# 00_BoardDiagramEntryConn.net
KiCad netlist of a schematic drawn in Altium Designer
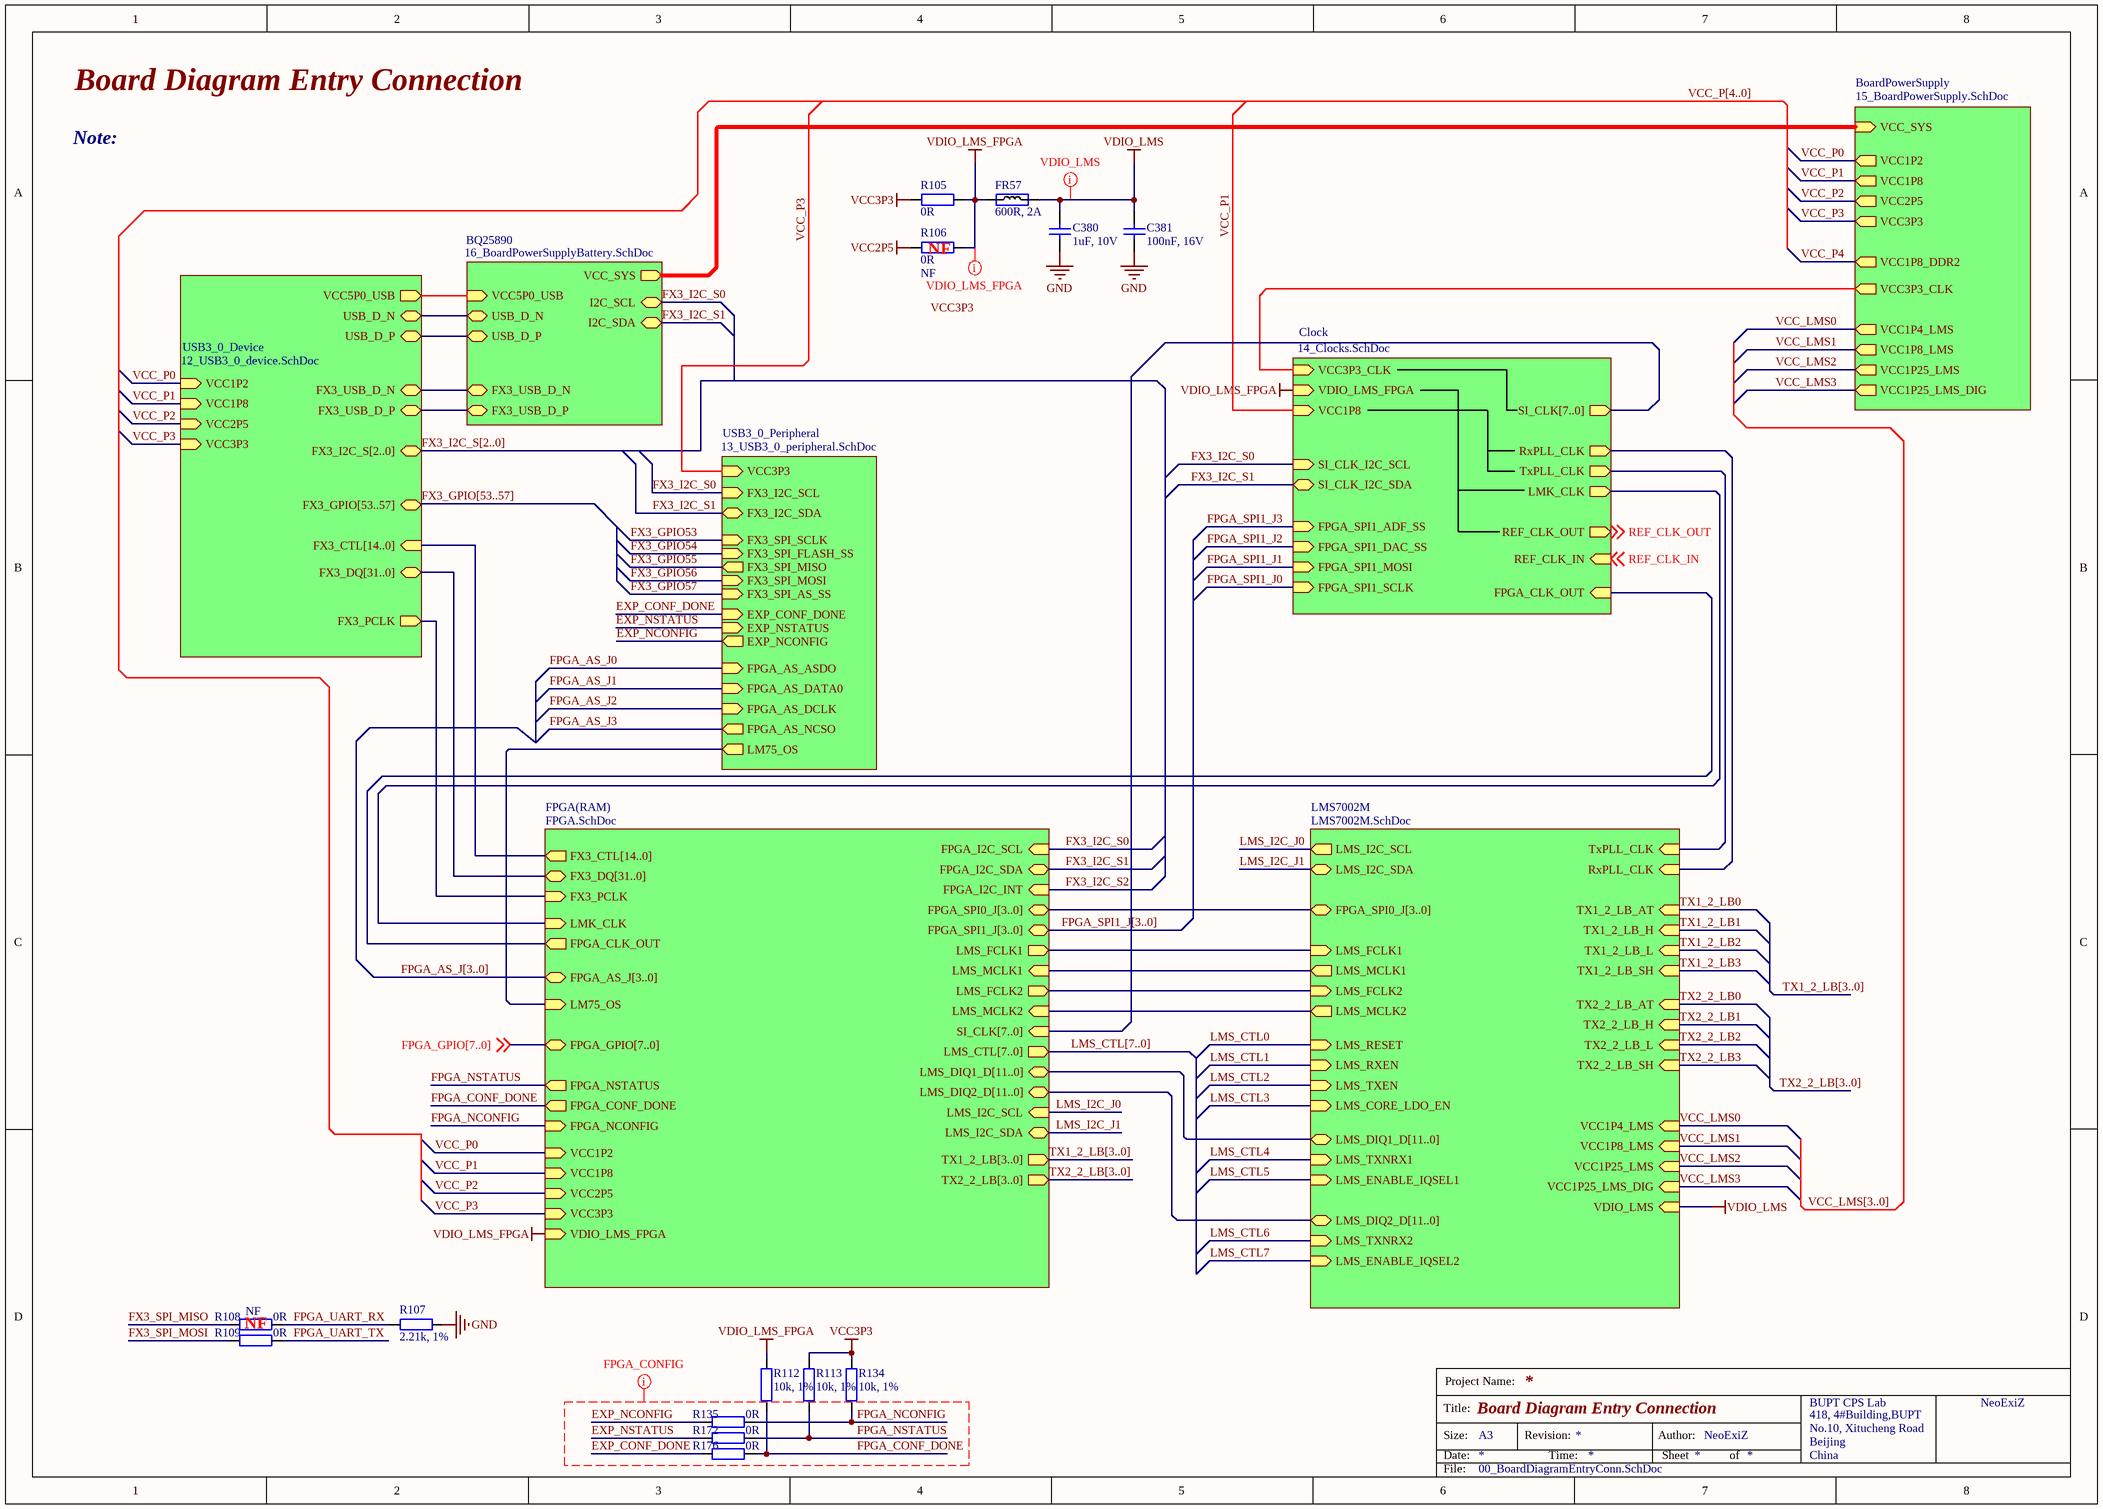
[diagram p0: 00_BoardDiagramEntryConn.SchDoc]

(export (version "E")
  (design (tool "Eeschema 10.0.6"))
  (components
    (comp (ref "C380")
      (value "1uF, 10V")
      (footprint "CAP0402")
      (fields (field (name "MANUFACTURER") "TDK"))
      (libsource (lib "LimeMicroAltiumLib_schLib") (part "Cap_0402"))
    )
    (comp (ref "C381")
      (value "100nF, 16V")
      (footprint "CAP0402")
      (fields
        (field (name "MANUFACTURER") "Murata Electronics")
        (field (name "TOLERANCE") "10 %")
        (field (name "MANUFACTURER PART NUMBER") "GRM155R71C104KA88D")
      )
      (libsource (lib "LimeMicroAltiumLib_schLib") (part "Cap_0402"))
    )
    (comp (ref "FR57")
      (value "600R, 2A")
      (footprint "RES0805")
      (fields (field (name "MANUFACTURER") "TDK Corporation"))
      (libsource (lib "LimeMicroAltiumLib_schLib") (part "Ferrite"))
    )
    (comp (ref "R105")
      (value "0R")
      (footprint "RES0402")
      (fields (field (name "MANUFACTURER") "Yageo") (field (name "TOLERANCE") "Jumper"))
      (libsource (lib "LimeMicroAltiumLib_schLib") (part "Res_0402"))
    )
    (comp (ref "R106")
      (value "0R")
      (footprint "RES0402")
      (fields
        (field (name "ASSEMBLY INFO") "NF")
        (field (name "MANUFACTURER") "Yageo")
        (field (name "TOLERANCE") "Jumper")
      )
      (libsource (lib "LimeMicroAltiumLib_schLib") (part "Res_0402"))
    )
    (comp (ref "R107")
      (value "2.21k, 1%")
      (footprint "RES0402")
      (fields (field (name "MANUFACTURER") "Stackpole Electronics Inc.") (field (name "TOLERANCE") "±1%"))
      (libsource (lib "LimeMicroAltiumLib_schLib") (part "Res_0402"))
    )
    (comp (ref "R108")
      (value "0R")
      (footprint "RES0402")
      (fields (field (name "MANUFACTURER") "Yageo") (field (name "ASSEMBLY INFO") "NF"))
      (libsource (lib "LimeFPGAboard_schLib") (part "Res_0402"))
    )
    (comp (ref "R109")
      (value "0R")
      (footprint "RES0402")
      (fields (field (name "MANUFACTURER") "Yageo"))
      (libsource (lib "LimeFPGAboard_schLib") (part "Res_0402"))
    )
    (comp (ref "R112")
      (value "10k, 1%")
      (footprint "RES0402")
      (fields (field (name "MANUFACTURER") "Yageo") (field (name "TOLERANCE") "±1%"))
      (libsource (lib "LimeMicroAltiumLib_schLib") (part "Res_0402"))
    )
    (comp (ref "R113")
      (value "10k, 1%")
      (footprint "RES0402")
      (fields (field (name "MANUFACTURER") "Yageo") (field (name "TOLERANCE") "±1%"))
      (libsource (lib "LimeMicroAltiumLib_schLib") (part "Res_0402"))
    )
    (comp (ref "R134")
      (value "10k, 1%")
      (footprint "RES0402")
      (fields (field (name "MANUFACTURER") "Yageo") (field (name "TOLERANCE") "±1%"))
      (libsource (lib "LimeMicroAltiumLib_schLib") (part "Res_0402"))
    )
    (comp (ref "R135")
      (value "0R")
      (footprint "RES0402")
      (fields (field (name "MANUFACTURER") "Yageo"))
      (libsource (lib "LimeFPGAboard_schLib") (part "Res_0402"))
    )
    (comp (ref "R172")
      (value "0R")
      (footprint "RES0402")
      (fields (field (name "MANUFACTURER") "Yageo"))
      (libsource (lib "LimeFPGAboard_schLib") (part "Res_0402"))
    )
    (comp (ref "R176")
      (value "0R")
      (footprint "RES0402")
      (fields (field (name "MANUFACTURER") "Yageo"))
      (libsource (lib "LimeFPGAboard_schLib") (part "Res_0402"))
    )
  )
  (nets
    (net (code "1") (name "/EXP_CONF_DONE") (class "Default")
      (node (ref "R176") (pin "1") (pinfunction "1_1") (pintype "passive"))
    )
    (net (code "2") (name "/EXP_NCONFIG") (class "Default")
      (node (ref "R135") (pin "1") (pinfunction "1_1") (pintype "passive"))
    )
    (net (code "3") (name "/EXP_NSTATUS") (class "Default")
      (node (ref "R172") (pin "1") (pinfunction "1_1") (pintype "passive"))
    )
    (net (code "10") (name "/FPGA_CONF_DONE") (class "Default")
      (node (ref "R112") (pin "2") (pinfunction "2_2") (pintype "passive"))
      (node (ref "R176") (pin "2") (pinfunction "2_2") (pintype "passive"))
    )
    (net (code "11") (name "/FPGA_NCONFIG") (class "Default")
      (node (ref "R134") (pin "2") (pinfunction "2_2") (pintype "passive"))
      (node (ref "R135") (pin "2") (pinfunction "2_2") (pintype "passive"))
    )
    (net (code "12") (name "/FPGA_NSTATUS") (class "Default")
      (node (ref "R113") (pin "2") (pinfunction "2_2") (pintype "passive"))
      (node (ref "R172") (pin "2") (pinfunction "2_2") (pintype "passive"))
    )
    (net (code "19") (name "/FPGA_UART_RX") (class "Default")
      (node (ref "R107") (pin "2") (pinfunction "2_2") (pintype "passive"))
      (node (ref "R108") (pin "2") (pinfunction "2_2") (pintype "passive"))
    )
    (net (code "20") (name "/FPGA_UART_TX") (class "Default")
      (node (ref "R109") (pin "2") (pinfunction "2_2") (pintype "passive"))
    )
    (net (code "34") (name "/FX3_SPI_MISO") (class "Default")
      (node (ref "R108") (pin "1") (pinfunction "1_1") (pintype "passive"))
    )
    (net (code "35") (name "/FX3_SPI_MOSI") (class "Default")
      (node (ref "R109") (pin "1") (pinfunction "1_1") (pintype "passive"))
    )
    (net (code "87") (name "GND") (class "Default")
      (node (ref "C380") (pin "1") (pinfunction "1_1") (pintype "passive"))
      (node (ref "C381") (pin "2") (pinfunction "2_2") (pintype "passive"))
      (node (ref "R107") (pin "1") (pinfunction "1_1") (pintype "passive"))
    )
    (net (code "90") (name "VCC2P5") (class "Default")
      (node (ref "R106") (pin "2") (pinfunction "2_2") (pintype "passive"))
    )
    (net (code "91") (name "VCC3P3") (class "Default")
      (node (ref "R105") (pin "2") (pinfunction "2_2") (pintype "passive"))
      (node (ref "R113") (pin "1") (pinfunction "1_1") (pintype "passive"))
      (node (ref "R134") (pin "1") (pinfunction "1_1") (pintype "passive"))
    )
    (net (code "92") (name "VDIO_LMS") (class "Default")
      (node (ref "C380") (pin "2") (pinfunction "2_2") (pintype "passive"))
      (node (ref "C381") (pin "1") (pinfunction "1_1") (pintype "passive"))
      (node (ref "FR57") (pin "2") (pinfunction "2_2") (pintype "passive"))
    )
    (net (code "93") (name "VDIO_LMS_FPGA") (class "Default")
      (node (ref "FR57") (pin "1") (pinfunction "1_1") (pintype "passive"))
      (node (ref "R105") (pin "1") (pinfunction "1_1") (pintype "passive"))
      (node (ref "R106") (pin "1") (pinfunction "1_1") (pintype "passive"))
      (node (ref "R112") (pin "1") (pinfunction "1_1") (pintype "passive"))
    )
  )
)
